# PLD_Connectors.net
KiCad netlist of a schematic drawn in Altium Designer
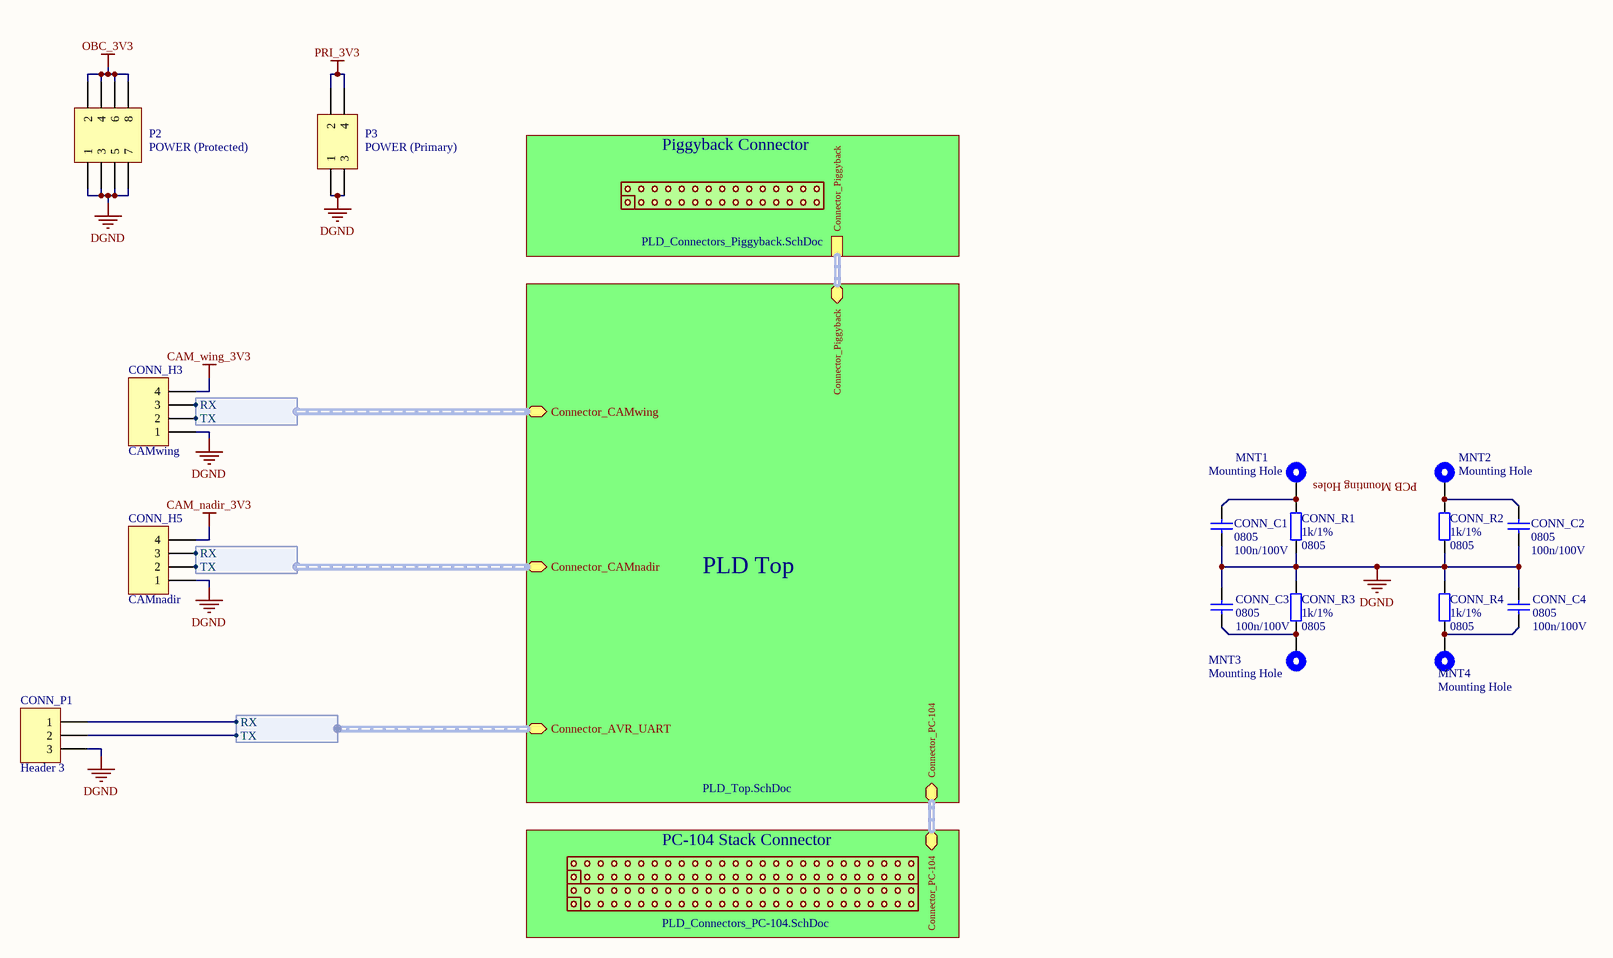
[diagram p0: PLD_Connectors.SchDoc]

(export (version "E")
  (design (tool "Eeschema 10.0.6"))
  (components
    (comp (ref "CONN_C1")
      (value "100n/100V")
      (footprint "SMD_Capacitor_0805")
      (description "Ceramic Cap Kemet COTS 100n/100V X7R 0805")
      (fields
        (field (name "MANUFACTURERPARTNUMBER") "C0805T104K1RCLTU")
        (field (name "MANUFACTURER") "Kemet")
        (field (name "PACKAGE") "0805")
      )
      (libsource (lib "capacitors") (part "Cer_C0805T104K1RCLTU"))
    )
    (comp (ref "CONN_C2")
      (value "100n/100V")
      (footprint "SMD_Capacitor_0805")
      (description "Ceramic Cap Kemet COTS 100n/100V X7R 0805")
      (fields
        (field (name "MANUFACTURERPARTNUMBER") "C0805T104K1RCLTU")
        (field (name "MANUFACTURER") "Kemet")
        (field (name "PACKAGE") "0805")
      )
      (libsource (lib "capacitors") (part "Cer_C0805T104K1RCLTU"))
    )
    (comp (ref "CONN_C3")
      (value "100n/100V")
      (footprint "SMD_Capacitor_0805")
      (description "Ceramic Cap Kemet COTS 100n/100V X7R 0805")
      (fields
        (field (name "MANUFACTURERPARTNUMBER") "C0805T104K1RCLTU")
        (field (name "MANUFACTURER") "Kemet")
        (field (name "PACKAGE") "0805")
      )
      (libsource (lib "capacitors") (part "Cer_C0805T104K1RCLTU"))
    )
    (comp (ref "CONN_C4")
      (value "100n/100V")
      (footprint "SMD_Capacitor_0805")
      (description "Ceramic Cap Kemet COTS 100n/100V X7R 0805")
      (fields
        (field (name "MANUFACTURERPARTNUMBER") "C0805T104K1RCLTU")
        (field (name "MANUFACTURER") "Kemet")
        (field (name "PACKAGE") "0805")
      )
      (libsource (lib "capacitors") (part "Cer_C0805T104K1RCLTU"))
    )
    (comp (ref "CONN_H3")
      (value "CAMwing")
      (footprint "HEADER 1X4H Male")
      (description "Header, 4-Pin")
      (fields (field (name "PUBLISHER") "Altium Limited"))
      (libsource (lib "connectors_printed-circuit-board") (part "Header 4"))
    )
    (comp (ref "CONN_H5")
      (value "CAMnadir")
      (footprint "HEADER 1X4H Male")
      (description "Header, 4-Pin")
      (fields (field (name "PUBLISHER") "Altium Limited"))
      (libsource (lib "connectors_printed-circuit-board") (part "Header 4"))
    )
    (comp (ref "CONN_P1")
      (value "Header 3")
      (footprint "HEADER1X3H Male")
      (description "Header, 3-Pin")
      (fields (field (name "PUBLISHER") "Altium Limited"))
      (libsource (lib "connectors_printed-circuit-board") (part "Header 3"))
    )
    (comp (ref "CONN_R1")
      (value "1k/1%")
      (footprint "SMD_Resistor_0805")
      (description "1k/1% Vishay CRCW 0805 Resistor. 125mW, 100ppm, 150V.")
      (fields
        (field (name "MANUFACTURER") "Vishay")
        (field (name "MANUFACTURERPARTNUMBER") "CRCW08051K00FKxxxx")
        (field (name "PACKAGE") "0805")
      )
      (libsource (lib "") (part "CRCW08051K00FKxxxx_1"))
    )
    (comp (ref "CONN_R2")
      (value "1k/1%")
      (footprint "SMD_Resistor_0805")
      (description "1k/1% Vishay CRCW 0805 Resistor. 125mW, 100ppm, 150V.")
      (fields
        (field (name "MANUFACTURER") "Vishay")
        (field (name "MANUFACTURERPARTNUMBER") "CRCW08051K00FKxxxx")
        (field (name "PACKAGE") "0805")
      )
      (libsource (lib "resistors") (part "CRCW08051K00FKxxxx"))
    )
    (comp (ref "CONN_R3")
      (value "1k/1%")
      (footprint "SMD_Resistor_0805")
      (description "1k/1% Vishay CRCW 0805 Resistor. 125mW, 100ppm, 150V.")
      (fields
        (field (name "MANUFACTURER") "Vishay")
        (field (name "MANUFACTURERPARTNUMBER") "CRCW08051K00FKxxxx")
        (field (name "PACKAGE") "0805")
      )
      (libsource (lib "") (part "CRCW08051K00FKxxxx_1"))
    )
    (comp (ref "CONN_R4")
      (value "1k/1%")
      (footprint "SMD_Resistor_0805")
      (description "1k/1% Vishay CRCW 0805 Resistor. 125mW, 100ppm, 150V.")
      (fields
        (field (name "MANUFACTURER") "Vishay")
        (field (name "MANUFACTURERPARTNUMBER") "CRCW08051K00FKxxxx")
        (field (name "PACKAGE") "0805")
      )
      (libsource (lib "resistors") (part "CRCW08051K00FKxxxx"))
    )
    (comp (ref "MNT1")
      (value "Mounting Hole")
      (footprint "PC-104_PcbMntHole_M3")
      (description "PCB Mounting Hole")
      (libsource (lib "connectors_printed-circuit-board") (part "MntHole"))
    )
    (comp (ref "MNT2")
      (value "Mounting Hole")
      (footprint "PC-104_PcbMntHole_M3")
      (description "PCB Mounting Hole")
      (libsource (lib "connectors_printed-circuit-board") (part "MntHole"))
    )
    (comp (ref "MNT3")
      (value "Mounting Hole")
      (footprint "PC-104_PcbMntHole_M3")
      (description "PCB Mounting Hole")
      (libsource (lib "connectors_printed-circuit-board") (part "MntHole"))
    )
    (comp (ref "MNT4")
      (value "Mounting Hole")
      (footprint "PC-104_PcbMntHole_M3")
      (description "PCB Mounting Hole")
      (libsource (lib "connectors_printed-circuit-board") (part "MntHole"))
    )
    (comp (ref "P2")
      (value "POWER (Protected)")
      (footprint "HEADER 2X4 MALE")
      (description "Header, 4-Pin, Dual row")
      (fields (field (name "PUBLISHER") "Altium Limited"))
      (libsource (lib "connectors_printed-circuit-board") (part "Header 4X2"))
    )
    (comp (ref "P3")
      (value "POWER (Primary)")
      (footprint "HDR2X2")
      (description "Header, 2-Pin, Dual row")
      (fields (field (name "PUBLISHER") "Altium Limited"))
      (libsource (lib "connectors_printed-circuit-board") (part "Header 2X2"))
    )
  )
  (nets
    (net (code "7") (name "CAM_nadir_3V3") (class "Default")
      (node (ref "CONN_H5") (pin "4") (pinfunction "4_4") (pintype "passive"))
    )
    (net (code "8") (name "CAM_wing_3V3") (class "Default")
      (node (ref "CONN_H3") (pin "4") (pinfunction "4_4") (pintype "passive"))
    )
    (net (code "9") (name "DGND") (class "Default")
      (node (ref "CONN_C1") (pin "1") (pinfunction "1_1") (pintype "passive"))
      (node (ref "CONN_C2") (pin "1") (pinfunction "1_1") (pintype "passive"))
      (node (ref "CONN_C3") (pin "2") (pinfunction "2_2") (pintype "passive"))
      (node (ref "CONN_C4") (pin "2") (pinfunction "2_2") (pintype "passive"))
      (node (ref "CONN_H3") (pin "1") (pinfunction "1_1") (pintype "passive"))
      (node (ref "CONN_H5") (pin "1") (pinfunction "1_1") (pintype "passive"))
      (node (ref "CONN_P1") (pin "3") (pinfunction "3_3") (pintype "passive"))
      (node (ref "CONN_R1") (pin "1") (pinfunction "1_1") (pintype "passive"))
      (node (ref "CONN_R2") (pin "1") (pinfunction "1_1") (pintype "passive"))
      (node (ref "CONN_R3") (pin "2") (pinfunction "2_2") (pintype "passive"))
      (node (ref "CONN_R4") (pin "2") (pinfunction "2_2") (pintype "passive"))
      (node (ref "P2") (pin "1") (pinfunction "1_1") (pintype "passive"))
      (node (ref "P2") (pin "3") (pinfunction "3_3") (pintype "passive"))
      (node (ref "P2") (pin "5") (pinfunction "5_5") (pintype "passive"))
      (node (ref "P2") (pin "7") (pinfunction "7_7") (pintype "passive"))
      (node (ref "P3") (pin "1") (pinfunction "1_1") (pintype "passive"))
      (node (ref "P3") (pin "3") (pinfunction "3_3") (pintype "passive"))
    )
    (net (code "10") (name "Net-(CONN_C1-Pad2)") (class "Default")
      (node (ref "CONN_C1") (pin "2") (pinfunction "2_2") (pintype "passive"))
      (node (ref "CONN_R1") (pin "2") (pinfunction "2_2") (pintype "passive"))
      (node (ref "MNT1") (pin "1") (pinfunction "1_1") (pintype "passive"))
    )
    (net (code "11") (name "Net-(CONN_C2-Pad2)") (class "Default")
      (node (ref "CONN_C2") (pin "2") (pinfunction "2_2") (pintype "passive"))
      (node (ref "CONN_R2") (pin "2") (pinfunction "2_2") (pintype "passive"))
      (node (ref "MNT2") (pin "1") (pinfunction "1_1") (pintype "passive"))
    )
    (net (code "12") (name "Net-(CONN_C3-Pad1)") (class "Default")
      (node (ref "CONN_C3") (pin "1") (pinfunction "1_1") (pintype "passive"))
      (node (ref "CONN_R3") (pin "1") (pinfunction "1_1") (pintype "passive"))
      (node (ref "MNT3") (pin "1") (pinfunction "1_1") (pintype "passive"))
    )
    (net (code "13") (name "Net-(CONN_C4-Pad1)") (class "Default")
      (node (ref "CONN_C4") (pin "1") (pinfunction "1_1") (pintype "passive"))
      (node (ref "CONN_R4") (pin "1") (pinfunction "1_1") (pintype "passive"))
      (node (ref "MNT4") (pin "1") (pinfunction "1_1") (pintype "passive"))
    )
    (net (code "14") (name "OBC_3V3") (class "Default")
      (node (ref "P2") (pin "2") (pinfunction "2_2") (pintype "passive"))
      (node (ref "P2") (pin "4") (pinfunction "4_4") (pintype "passive"))
      (node (ref "P2") (pin "6") (pinfunction "6_6") (pintype "passive"))
      (node (ref "P2") (pin "8") (pinfunction "8_8") (pintype "passive"))
    )
    (net (code "15") (name "PRI_3V3") (class "Default")
      (node (ref "P3") (pin "2") (pinfunction "2_2") (pintype "passive"))
      (node (ref "P3") (pin "4") (pinfunction "4_4") (pintype "passive"))
    )
    (net (code "16") (name "unconnected-(CONN_H3-Pad2)") (class "Default")
      (node (ref "CONN_H3") (pin "2") (pinfunction "2_2") (pintype "passive"))
    )
    (net (code "17") (name "unconnected-(CONN_H3-Pad3)") (class "Default")
      (node (ref "CONN_H3") (pin "3") (pinfunction "3_3") (pintype "passive"))
    )
    (net (code "18") (name "unconnected-(CONN_H5-Pad2)") (class "Default")
      (node (ref "CONN_H5") (pin "2") (pinfunction "2_2") (pintype "passive"))
    )
    (net (code "19") (name "unconnected-(CONN_H5-Pad3)") (class "Default")
      (node (ref "CONN_H5") (pin "3") (pinfunction "3_3") (pintype "passive"))
    )
    (net (code "20") (name "unconnected-(CONN_P1-Pad1)") (class "Default")
      (node (ref "CONN_P1") (pin "1") (pinfunction "1_1") (pintype "passive"))
    )
    (net (code "21") (name "unconnected-(CONN_P1-Pad2)") (class "Default")
      (node (ref "CONN_P1") (pin "2") (pinfunction "2_2") (pintype "passive"))
    )
  )
)
